# thermal.net
KiCad netlist of a schematic drawn in Altium Designer
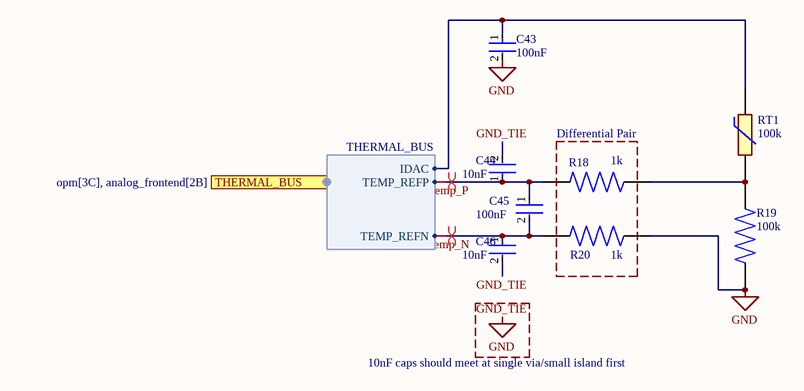
[diagram p0: thermal.SchDoc]

(export (version "E")
  (design (tool "Eeschema 10.0.6"))
  (components
    (comp (ref "C43")
      (value "100nF")
      (footprint "GRM3195C1H104JA05D")
      (description "50V 100nF C0G ±5% 1206 Multilayer Ceramic Capacitors MLCC - SMD/SMT ROHS")
      (fields
        (field (name "MANUFACTURER") "Murata")
        (field (name "MANUFACTURER PART NUMBER") "GRM3195C1H104JA05D")
      )
      (libsource (lib "opm_lib") (part "GRM3195C1H104JA05D"))
    )
    (comp (ref "C44")
      (value "10nF")
      (footprint "GRM1885C1H103JA01D")
      (description "Multilayer Ceramic Capacitor, Grm Series, 0.01 F, 5%, C0g / Np0, 50 V, 0603 [1608 Metric]")
      (fields
        (field (name "MANUFACTURER") "Murata")
        (field (name "MANUFACTURER PART NUMBER") "GRM1885C1H103JA01D")
      )
      (libsource (lib "opm_lib") (part "GRM1885C1H103JA01D"))
    )
    (comp (ref "C45")
      (value "100nF")
      (footprint "GRM3195C1H104JA05D")
      (description "50V 100nF C0G ±5% 1206 Multilayer Ceramic Capacitors MLCC - SMD/SMT ROHS")
      (fields
        (field (name "MANUFACTURER") "Murata")
        (field (name "MANUFACTURER PART NUMBER") "GRM3195C1H104JA05D")
      )
      (libsource (lib "opm_lib") (part "GRM3195C1H104JA05D"))
    )
    (comp (ref "C46")
      (value "10nF")
      (footprint "GRM1885C1H103JA01D")
      (description "Multilayer Ceramic Capacitor, Grm Series, 0.01 F, 5%, C0g / Np0, 50 V, 0603 [1608 Metric]")
      (fields
        (field (name "MANUFACTURER") "Murata")
        (field (name "MANUFACTURER PART NUMBER") "GRM1885C1H103JA01D")
      )
      (libsource (lib "opm_lib") (part "GRM1885C1H103JA01D"))
    )
    (comp (ref "R18")
      (value "1k")
      (footprint "RESC1508X55N")
      (description "Fixed Resistor, Thin Film, 0.1W, 1000ohm, 75V, 0.1% +/-Tol, 15ppm/Cel, Surface Mount, 0603")
      (fields
        (field (name "MANUFACTURER") "Vishay")
        (field (name "MANUFACTURER PART NUMBER") "TNPW06031K00BXEN")
      )
      (libsource (lib "opm_lib") (part "TNPW06031K00BXEN"))
    )
    (comp (ref "R19")
      (value "100k")
      (footprint "RESC1508X55N")
      (description "Fixed Resistor, Thin Film, 0.1W, 100000ohm, 75V, 0.1% +/-Tol, 15ppm/Cel, Surface Mount, 0603")
      (fields
        (field (name "MANUFACTURER") "Vishay")
        (field (name "MANUFACTURER PART NUMBER") "TNPW0603100KBXEN")
      )
      (libsource (lib "opm_lib") (part "TNPW0603100KBXEN"))
    )
    (comp (ref "R20")
      (value "1k")
      (footprint "RESC1508X55N")
      (description "Fixed Resistor, Thin Film, 0.1W, 1000ohm, 75V, 0.1% +/-Tol, 15ppm/Cel, Surface Mount, 0603")
      (fields
        (field (name "MANUFACTURER") "Vishay")
        (field (name "MANUFACTURER PART NUMBER") "TNPW06031K00BXEN")
      )
      (libsource (lib "opm_lib") (part "TNPW06031K00BXEN"))
    )
    (comp (ref "RT1")
      (value "100k")
      (footprint "104JT-025")
      (description "NTC Thermistor, 100000ohm, Through Hole Mount")
      (fields (field (name "MANUFACTURER") "Semitec") (field (name "MANUFACTURER PART NUMBER") "104JT-025"))
      (libsource (lib "opm_lib") (part "104JT-025"))
    )
  )
  (nets
    (net (code "2") (name "/Temp_N") (class "Default")
      (node (ref "C45") (pin "2") (pinfunction "2_2") (pintype "passive"))
      (node (ref "C46") (pin "1") (pinfunction "1_1") (pintype "passive"))
      (node (ref "R20") (pin "1") (pinfunction "1_1") (pintype "passive"))
    )
    (net (code "3") (name "/Temp_P") (class "Default")
      (node (ref "C44") (pin "1") (pinfunction "1_1") (pintype "passive"))
      (node (ref "C45") (pin "1") (pinfunction "1_1") (pintype "passive"))
      (node (ref "R18") (pin "1") (pinfunction "1_1") (pintype "passive"))
    )
    (net (code "5") (name "GND") (class "Default")
      (node (ref "C43") (pin "2") (pinfunction "2_2") (pintype "passive"))
      (node (ref "C44") (pin "2") (pinfunction "2_2") (pintype "passive"))
      (node (ref "C46") (pin "2") (pinfunction "2_2") (pintype "passive"))
      (node (ref "R19") (pin "2") (pinfunction "2_2") (pintype "passive"))
      (node (ref "R20") (pin "2") (pinfunction "2_2") (pintype "passive"))
    )
    (net (code "6") (name "Net-(C43-Pad1)") (class "Default")
      (node (ref "C43") (pin "1") (pinfunction "1_1") (pintype "passive"))
      (node (ref "RT1") (pin "1") (pinfunction "1_1") (pintype "passive"))
    )
    (net (code "7") (name "Net-(R18-Pad2)") (class "Default")
      (node (ref "R18") (pin "2") (pinfunction "2_2") (pintype "passive"))
      (node (ref "R19") (pin "1") (pinfunction "1_1") (pintype "passive"))
      (node (ref "RT1") (pin "2") (pinfunction "2_2") (pintype "passive"))
    )
  )
)
